# RGB_1_1b.net
KiCad netlist of a schematic drawn in EAGLE
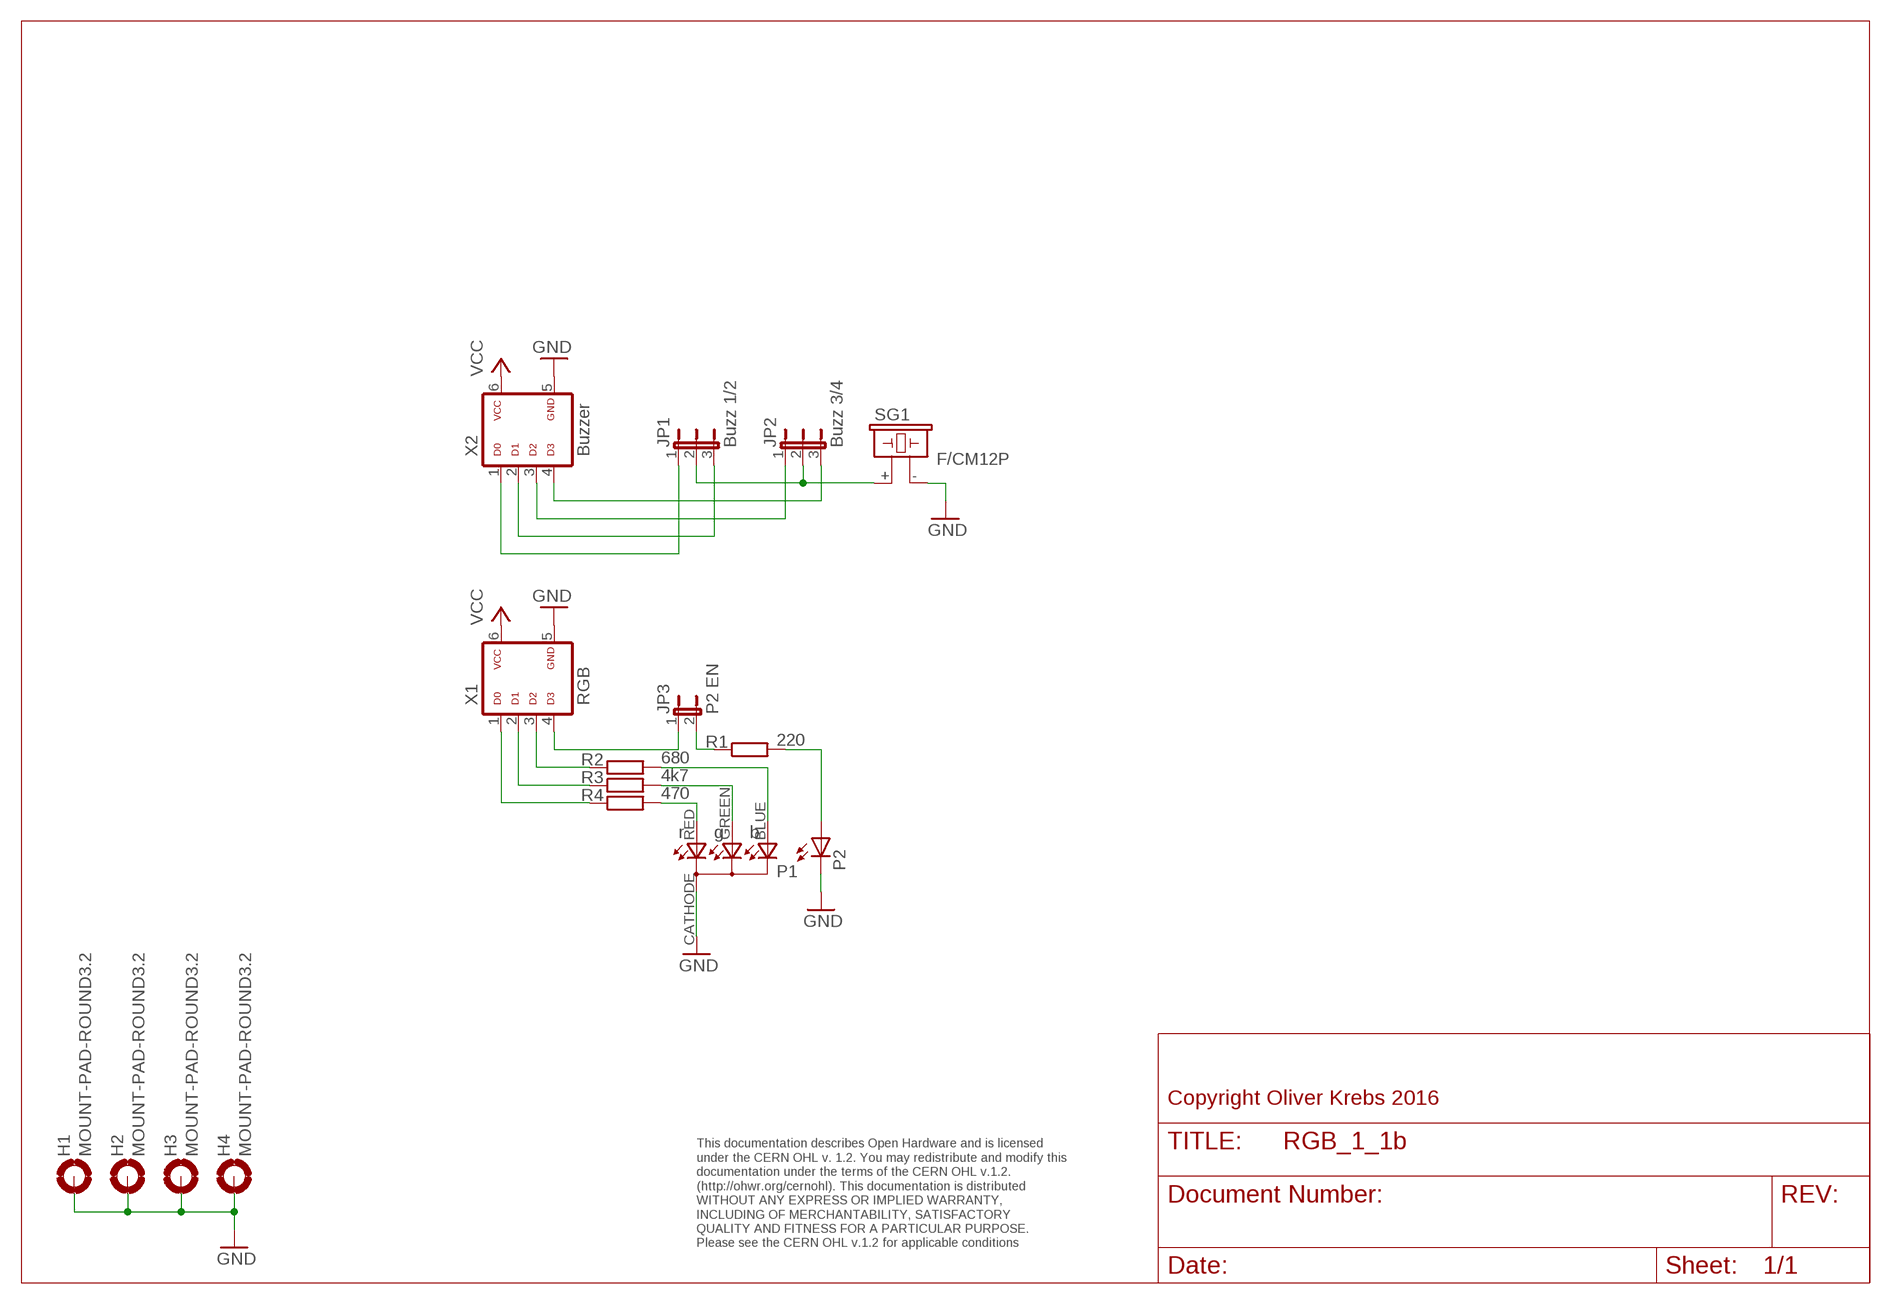
[diagram p0: schematic, sheet 1]

(export (version "E")
  (design (tool "Eeschema 10.0.6"))
  (components
    (comp (ref "H1")
      (value "MOUNT-PAD-ROUND3.2")
      (footprint "eagle-import:3,2-PAD")
      (libsource (lib "eagle-import") (part "MOUNT-PAD-ROUND3.2"))
    )
    (comp (ref "H2")
      (value "MOUNT-PAD-ROUND3.2")
      (footprint "eagle-import:3,2-PAD")
      (libsource (lib "eagle-import") (part "MOUNT-PAD-ROUND3.2"))
    )
    (comp (ref "H3")
      (value "MOUNT-PAD-ROUND3.2")
      (footprint "eagle-import:3,2-PAD")
      (libsource (lib "eagle-import") (part "MOUNT-PAD-ROUND3.2"))
    )
    (comp (ref "H4")
      (value "MOUNT-PAD-ROUND3.2")
      (footprint "eagle-import:3,2-PAD")
      (libsource (lib "eagle-import") (part "MOUNT-PAD-ROUND3.2"))
    )
    (comp (ref "JP1")
      (value "Buzz 1/2")
      (footprint "eagle-import:JP2")
      (libsource (lib "eagle-import") (part "JP2E"))
    )
    (comp (ref "JP2")
      (value "Buzz 3/4")
      (footprint "eagle-import:JP2")
      (libsource (lib "eagle-import") (part "JP2E"))
    )
    (comp (ref "JP3")
      (value "P2 EN")
      (footprint "eagle-import:JP1")
      (libsource (lib "eagle-import") (part "JP1E"))
    )
    (comp (ref "P1")
      (value "RGB-5MM")
      (footprint "eagle-import:RGB5MM")
      (libsource (lib "eagle-import") (part "RGB-5MM"))
    )
    (comp (ref "P2")
      (value "LED5MM")
      (footprint "eagle-import:LED5MM")
      (libsource (lib "eagle-import") (part "LED5MM"))
    )
    (comp (ref "R1")
      (value "220")
      (footprint "eagle-import:0207_10")
      (libsource (lib "eagle-import") (part "R-EU_0207/10"))
    )
    (comp (ref "R2")
      (value "680")
      (footprint "eagle-import:0207_10")
      (libsource (lib "eagle-import") (part "R-EU_0207/10"))
    )
    (comp (ref "R3")
      (value "4k7")
      (footprint "eagle-import:0207_10")
      (libsource (lib "eagle-import") (part "R-EU_0207/10"))
    )
    (comp (ref "R4")
      (value "470")
      (footprint "eagle-import:0207_10")
      (libsource (lib "eagle-import") (part "R-EU_0207/10"))
    )
    (comp (ref "SG1")
      (value "F/CM12P")
      (footprint "eagle-import:F_CM12P")
      (libsource (lib "eagle-import") (part "F/CM12P"))
    )
    (comp (ref "X1")
      (value "RGB")
      (footprint "eagle-import:ML-6")
      (libsource (lib "eagle-import") (part "ML6D"))
    )
    (comp (ref "X2")
      (value "Buzzer")
      (footprint "eagle-import:ML-6")
      (libsource (lib "eagle-import") (part "ML6D"))
    )
  )
  (nets
    (net (code "1") (name "GND") (class "Default")
      (node (ref "H1") (pin "B3,2") (pinfunction "MOUNT_B3,2") (pintype "passive"))
      (node (ref "H2") (pin "B3,2") (pinfunction "MOUNT_B3,2") (pintype "passive"))
      (node (ref "H3") (pin "B3,2") (pinfunction "MOUNT_B3,2") (pintype "passive"))
      (node (ref "H4") (pin "B3,2") (pinfunction "MOUNT_B3,2") (pintype "passive"))
      (node (ref "P1") (pin "CATHODE") (pinfunction "CATHODE_CATHODE") (pintype "passive"))
      (node (ref "P2") (pin "K") (pinfunction "C_K") (pintype "passive"))
      (node (ref "SG1") (pin "-") (pinfunction "2_-") (pintype "passive"))
      (node (ref "X1") (pin "5") (pinfunction "5_5") (pintype "passive"))
      (node (ref "X2") (pin "5") (pinfunction "5_5") (pintype "passive"))
    )
    (net (code "2") (name "Net-(JP1-Pad1)") (class "Default")
      (node (ref "JP1") (pin "1") (pinfunction "1_1") (pintype "passive"))
      (node (ref "X2") (pin "1") (pinfunction "1_1") (pintype "passive"))
    )
    (net (code "3") (name "Net-(JP1-Pad3)") (class "Default")
      (node (ref "JP1") (pin "3") (pinfunction "3_3") (pintype "passive"))
      (node (ref "X2") (pin "2") (pinfunction "2_2") (pintype "passive"))
    )
    (net (code "4") (name "Net-(JP2-Pad1)") (class "Default")
      (node (ref "JP2") (pin "1") (pinfunction "1_1") (pintype "passive"))
      (node (ref "X2") (pin "3") (pinfunction "3_3") (pintype "passive"))
    )
    (net (code "5") (name "Net-(JP2-Pad3)") (class "Default")
      (node (ref "JP2") (pin "3") (pinfunction "3_3") (pintype "passive"))
      (node (ref "X2") (pin "4") (pinfunction "4_4") (pintype "passive"))
    )
    (net (code "6") (name "Net-(JP3-Pad1)") (class "Default")
      (node (ref "JP3") (pin "1") (pinfunction "1_1") (pintype "passive"))
      (node (ref "X1") (pin "4") (pinfunction "4_4") (pintype "passive"))
    )
    (net (code "7") (name "Net-(JP3-Pad2)") (class "Default")
      (node (ref "JP3") (pin "2") (pinfunction "2_2") (pintype "passive"))
      (node (ref "R1") (pin "1") (pinfunction "1_1") (pintype "passive"))
    )
    (net (code "8") (name "Net-(P1-A-BLUE)") (class "Default")
      (node (ref "P1") (pin "BLUE") (pinfunction "A-BLUE_BLUE") (pintype "passive"))
      (node (ref "R2") (pin "2") (pinfunction "2_2") (pintype "passive"))
    )
    (net (code "9") (name "Net-(P1-A-GREEN)") (class "Default")
      (node (ref "P1") (pin "GREEN") (pinfunction "A-GREEN_GREEN") (pintype "passive"))
      (node (ref "R3") (pin "2") (pinfunction "2_2") (pintype "passive"))
    )
    (net (code "10") (name "Net-(P1-A-RED)") (class "Default")
      (node (ref "P1") (pin "RED") (pinfunction "A-RED_RED") (pintype "passive"))
      (node (ref "R4") (pin "2") (pinfunction "2_2") (pintype "passive"))
    )
    (net (code "11") (name "Net-(P2-PadA)") (class "Default")
      (node (ref "P2") (pin "A") (pinfunction "A_A") (pintype "passive"))
      (node (ref "R1") (pin "2") (pinfunction "2_2") (pintype "passive"))
    )
    (net (code "12") (name "Net-(R2-Pad1)") (class "Default")
      (node (ref "R2") (pin "1") (pinfunction "1_1") (pintype "passive"))
      (node (ref "X1") (pin "3") (pinfunction "3_3") (pintype "passive"))
    )
    (net (code "13") (name "Net-(R3-Pad1)") (class "Default")
      (node (ref "R3") (pin "1") (pinfunction "1_1") (pintype "passive"))
      (node (ref "X1") (pin "2") (pinfunction "2_2") (pintype "passive"))
    )
    (net (code "14") (name "Net-(R4-Pad1)") (class "Default")
      (node (ref "R4") (pin "1") (pinfunction "1_1") (pintype "passive"))
      (node (ref "X1") (pin "1") (pinfunction "1_1") (pintype "passive"))
    )
    (net (code "15") (name "Net-(SG1-1)") (class "Default")
      (node (ref "JP1") (pin "2") (pinfunction "2_2") (pintype "passive"))
      (node (ref "JP2") (pin "2") (pinfunction "2_2") (pintype "passive"))
      (node (ref "SG1") (pin "+") (pinfunction "1_+") (pintype "passive"))
    )
    (net (code "16") (name "VCC") (class "Default")
      (node (ref "X1") (pin "6") (pinfunction "6_6") (pintype "passive"))
      (node (ref "X2") (pin "6") (pinfunction "6_6") (pintype "passive"))
    )
  )
)
